# USB_Hub.net
KiCad netlist of a schematic drawn in Altium Designer
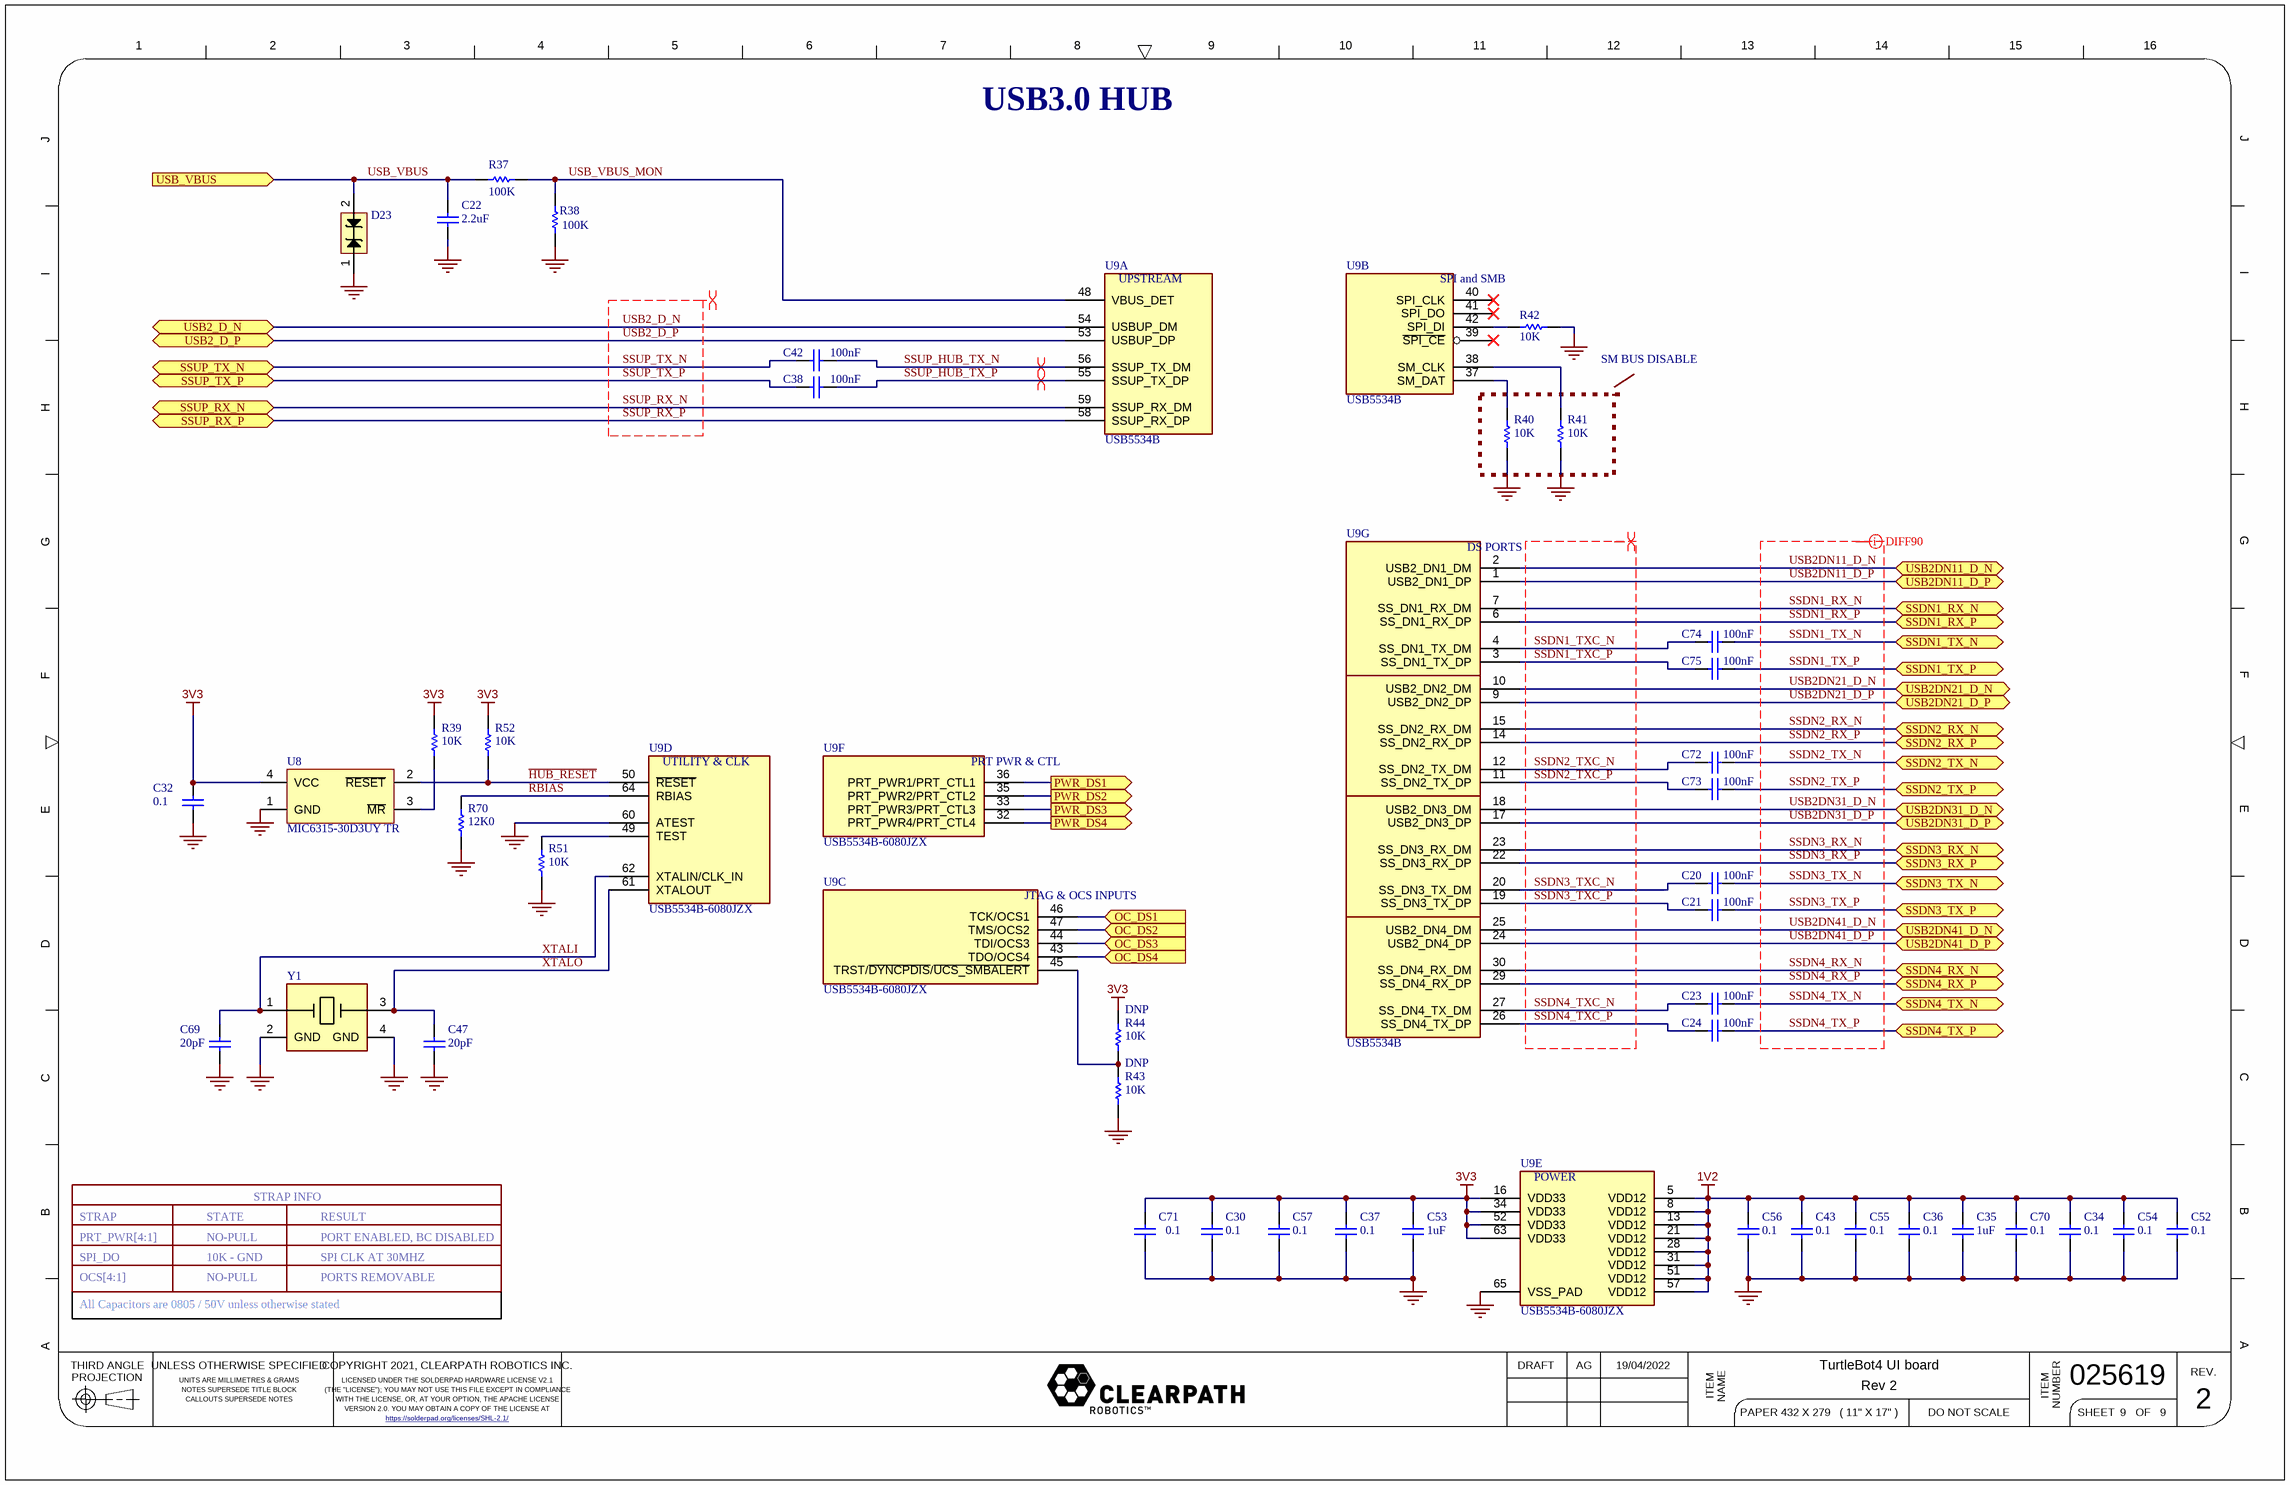
[diagram p0: USB Hub.SchDoc]

(export (version "E")
  (design (tool "Eeschema 10.0.6"))
  (components
    (comp (ref "C20")
      (value "100nF")
      (footprint "CAP 1608[0603]")
      (description "Capacitor")
      (fields (field (name "TOLERANCE") "10%") (field (name "VOLTAGE") "25V"))
      (libsource (lib "CPR_CommonDevices") (part "Capacitor _SMT"))
    )
    (comp (ref "C21")
      (value "100nF")
      (footprint "CAP 1608[0603]")
      (description "Capacitor")
      (fields (field (name "TOLERANCE") "10%") (field (name "VOLTAGE") "25V"))
      (libsource (lib "CPR_CommonDevices") (part "Capacitor _SMT"))
    )
    (comp (ref "C22")
      (value "2.2uF")
      (footprint "C0805")
      (description "Capacitor")
      (fields (field (name "TOLERANCE") "-20 +80") (field (name "VOLTAGE") "50V"))
      (libsource (lib "CPR_CommonDevices") (part "Capacitor _SMT"))
    )
    (comp (ref "C23")
      (value "100nF")
      (footprint "CAP 1608[0603]")
      (description "Capacitor")
      (fields (field (name "TOLERANCE") "10%") (field (name "VOLTAGE") "25V"))
      (libsource (lib "CPR_CommonDevices") (part "Capacitor _SMT"))
    )
    (comp (ref "C24")
      (value "100nF")
      (footprint "CAP 1608[0603]")
      (description "Capacitor")
      (fields (field (name "TOLERANCE") "10%") (field (name "VOLTAGE") "25V"))
      (libsource (lib "CPR_CommonDevices") (part "Capacitor _SMT"))
    )
    (comp (ref "C30")
      (value "0.1")
      (footprint "C0805")
      (description "Capacitor")
      (fields (field (name "TOLERANCE") "10%") (field (name "VOLTAGE") "50V"))
      (libsource (lib "CPR_CommonDevices") (part "Capacitor _SMT"))
    )
    (comp (ref "C32")
      (value "0.1")
      (footprint "C0805")
      (description "Capacitor")
      (fields (field (name "TOLERANCE") "10%") (field (name "VOLTAGE") "50V"))
      (libsource (lib "CPR_CommonDevices") (part "Capacitor _SMT"))
    )
    (comp (ref "C34")
      (value "0.1")
      (footprint "C0805")
      (description "Capacitor")
      (fields (field (name "TOLERANCE") "10%") (field (name "VOLTAGE") "50V"))
      (libsource (lib "CPR_CommonDevices") (part "Capacitor _SMT"))
    )
    (comp (ref "C35")
      (value "1uF")
      (footprint "C0805")
      (description "Capacitor")
      (fields (field (name "TOLERANCE") "-20 +80") (field (name "VOLTAGE") "50V"))
      (libsource (lib "CPR_CommonDevices") (part "Capacitor _SMT"))
    )
    (comp (ref "C36")
      (value "0.1")
      (footprint "C0805")
      (description "Capacitor")
      (fields (field (name "TOLERANCE") "10%") (field (name "VOLTAGE") "50V"))
      (libsource (lib "CPR_CommonDevices") (part "Capacitor _SMT"))
    )
    (comp (ref "C37")
      (value "0.1")
      (footprint "C0805")
      (description "Capacitor")
      (fields (field (name "TOLERANCE") "10%") (field (name "VOLTAGE") "50V"))
      (libsource (lib "CPR_CommonDevices") (part "Capacitor _SMT"))
    )
    (comp (ref "C38")
      (value "100nF")
      (footprint "CAP 1608[0603]")
      (description "Capacitor")
      (fields (field (name "TOLERANCE") "10%") (field (name "VOLTAGE") "25V"))
      (libsource (lib "CPR_CommonDevices") (part "Capacitor _SMT"))
    )
    (comp (ref "C42")
      (value "100nF")
      (footprint "CAP 1608[0603]")
      (description "Capacitor")
      (fields (field (name "TOLERANCE") "10%") (field (name "VOLTAGE") "25V"))
      (libsource (lib "CPR_CommonDevices") (part "Capacitor _SMT"))
    )
    (comp (ref "C43")
      (value "0.1")
      (footprint "C0805")
      (description "Capacitor")
      (fields (field (name "TOLERANCE") "10%") (field (name "VOLTAGE") "50V"))
      (libsource (lib "CPR_CommonDevices") (part "Capacitor _SMT"))
    )
    (comp (ref "C47")
      (value "20pF")
      (footprint "C0805")
      (description "Capacitor")
      (fields (field (name "TOLERANCE") "10%") (field (name "VOLTAGE") "50V"))
      (libsource (lib "CPR_CommonDevices") (part "Capacitor _SMT"))
    )
    (comp (ref "C52")
      (value "0.1")
      (footprint "C0805")
      (description "Capacitor")
      (fields (field (name "TOLERANCE") "10%") (field (name "VOLTAGE") "50V"))
      (libsource (lib "CPR_CommonDevices") (part "Capacitor _SMT"))
    )
    (comp (ref "C53")
      (value "1uF")
      (footprint "C0805")
      (description "Capacitor")
      (fields (field (name "TOLERANCE") "-20 +80") (field (name "VOLTAGE") "50V"))
      (libsource (lib "CPR_CommonDevices") (part "Capacitor _SMT"))
    )
    (comp (ref "C54")
      (value "0.1")
      (footprint "C0805")
      (description "Capacitor")
      (fields (field (name "TOLERANCE") "10%") (field (name "VOLTAGE") "50V"))
      (libsource (lib "CPR_CommonDevices") (part "Capacitor _SMT"))
    )
    (comp (ref "C55")
      (value "0.1")
      (footprint "C0805")
      (description "Capacitor")
      (fields (field (name "TOLERANCE") "10%") (field (name "VOLTAGE") "50V"))
      (libsource (lib "CPR_CommonDevices") (part "Capacitor _SMT"))
    )
    (comp (ref "C56")
      (value "0.1")
      (footprint "C0805")
      (description "Capacitor")
      (fields (field (name "TOLERANCE") "10%") (field (name "VOLTAGE") "50V"))
      (libsource (lib "CPR_CommonDevices") (part "Capacitor _SMT"))
    )
    (comp (ref "C57")
      (value "0.1")
      (footprint "C0805")
      (description "Capacitor")
      (fields (field (name "TOLERANCE") "10%") (field (name "VOLTAGE") "50V"))
      (libsource (lib "CPR_CommonDevices") (part "Capacitor _SMT"))
    )
    (comp (ref "C69")
      (value "20pF")
      (footprint "C0805")
      (description "Capacitor")
      (fields (field (name "TOLERANCE") "10%") (field (name "VOLTAGE") "50V"))
      (libsource (lib "CPR_CommonDevices") (part "Capacitor _SMT"))
    )
    (comp (ref "C70")
      (value "0.1")
      (footprint "C0805")
      (description "Capacitor")
      (fields (field (name "TOLERANCE") "10%") (field (name "VOLTAGE") "50V"))
      (libsource (lib "CPR_CommonDevices") (part "Capacitor _SMT"))
    )
    (comp (ref "C71")
      (value "0.1")
      (footprint "C0805")
      (description "Capacitor")
      (fields (field (name "TOLERANCE") "10%") (field (name "VOLTAGE") "50V"))
      (libsource (lib "CPR_CommonDevices") (part "Capacitor _SMT"))
    )
    (comp (ref "C72")
      (value "100nF")
      (footprint "CAP 1608[0603]")
      (description "Capacitor")
      (fields (field (name "TOLERANCE") "10%") (field (name "VOLTAGE") "25V"))
      (libsource (lib "CPR_CommonDevices") (part "Capacitor _SMT"))
    )
    (comp (ref "C73")
      (value "100nF")
      (footprint "CAP 1608[0603]")
      (description "Capacitor")
      (fields (field (name "TOLERANCE") "10%") (field (name "VOLTAGE") "25V"))
      (libsource (lib "CPR_CommonDevices") (part "Capacitor _SMT"))
    )
    (comp (ref "C74")
      (value "100nF")
      (footprint "CAP 1608[0603]")
      (description "Capacitor")
      (fields (field (name "TOLERANCE") "10%") (field (name "VOLTAGE") "25V"))
      (libsource (lib "CPR_CommonDevices") (part "Capacitor _SMT"))
    )
    (comp (ref "C75")
      (value "100nF")
      (footprint "CAP 1608[0603]")
      (description "Capacitor")
      (fields (field (name "TOLERANCE") "10%") (field (name "VOLTAGE") "25V"))
      (libsource (lib "CPR_CommonDevices") (part "Capacitor _SMT"))
    )
    (comp (ref "D23")
      (value "TVS DIODE BIDIR 15V SMC")
      (footprint "General PCB Library:DO-214AA")
      (description "TVS 600W 15V BI-DIR DO-214AA")
      (fields (field (name "MFG") "Littelfuse Inc."))
      (libsource (lib "SMBJ15CA") (part "TVS DIODE BIDIR 15V SMC"))
    )
    (comp (ref "R37")
      (value "100K")
      (footprint "R0805")
      (description "Resistor")
      (fields (field (name "TOLERANCE") "1%") (field (name "MFG") "Yageo"))
      (libsource (lib "CPR_CommonDevices") (part "Resistor_SMT"))
    )
    (comp (ref "R38")
      (value "100K")
      (footprint "R0805")
      (description "Resistor")
      (fields (field (name "TOLERANCE") "1%") (field (name "MFG") "Yageo"))
      (libsource (lib "CPR_CommonDevices") (part "Resistor_SMT"))
    )
    (comp (ref "R39")
      (value "10K")
      (footprint "R0805")
      (description "Resistor")
      (fields (field (name "TOLERANCE") "1%") (field (name "MFG") "Yageo"))
      (libsource (lib "CPR_CommonDevices") (part "Resistor_SMT"))
    )
    (comp (ref "R40")
      (value "10K")
      (footprint "R0805")
      (description "Resistor")
      (fields (field (name "TOLERANCE") "1%") (field (name "MFG") "Yageo"))
      (libsource (lib "CPR_CommonDevices") (part "Resistor_SMT"))
    )
    (comp (ref "R41")
      (value "10K")
      (footprint "R0805")
      (description "Resistor")
      (fields (field (name "TOLERANCE") "1%") (field (name "MFG") "Yageo"))
      (libsource (lib "CPR_CommonDevices") (part "Resistor_SMT"))
    )
    (comp (ref "R42")
      (value "10K")
      (footprint "R0805")
      (description "Resistor")
      (fields (field (name "TOLERANCE") "1%") (field (name "MFG") "Yageo"))
      (libsource (lib "CPR_CommonDevices") (part "Resistor_SMT"))
    )
    (comp (ref "R43")
      (value "10K")
      (footprint "R0805")
      (description "Resistor")
      (fields (field (name "TOLERANCE") "1%") (field (name "DNP") "DNP") (field (name "MFG") "Yageo"))
      (libsource (lib "CPR_CommonDevices") (part "Resistor_SMT"))
    )
    (comp (ref "R44")
      (value "10K")
      (footprint "R0805")
      (description "Resistor")
      (fields (field (name "TOLERANCE") "1%") (field (name "DNP") "DNP") (field (name "MFG") "Yageo"))
      (libsource (lib "CPR_CommonDevices") (part "Resistor_SMT"))
    )
    (comp (ref "R51")
      (value "10K")
      (footprint "R0805")
      (description "Resistor")
      (fields (field (name "TOLERANCE") "1%") (field (name "MFG") "Yageo"))
      (libsource (lib "CPR_CommonDevices") (part "Resistor_SMT"))
    )
    (comp (ref "R52")
      (value "10K")
      (footprint "R0805")
      (description "Resistor")
      (fields (field (name "TOLERANCE") "1%") (field (name "MFG") "Yageo"))
      (libsource (lib "CPR_CommonDevices") (part "Resistor_SMT"))
    )
    (comp (ref "R70")
      (value "12K0")
      (footprint "R0805")
      (description "Resistor")
      (fields (field (name "TOLERANCE") "1%") (field (name "MFG") "Yageo"))
      (libsource (lib "CPR_CommonDevices") (part "Resistor_SMT"))
    )
    (comp (ref "U8")
      (value "MIC6315")
      (footprint "SOT143 CPR")
      (description "IC RESET GEN 3.00V VTH SOT143-4")
      (fields (field (name "MFG") "Micrel") (field (name "MFG PN") "MIC6315-30D3UY TR"))
      (libsource (lib "Micrel") (part "MIC6315"))
    )
    (comp (ref "U9")
      (value "USB5534B")
      (footprint "QFN64_9x9_EP")
      (description "USB5534B 4-port USB3 hub")
      (fields (field (name "MFG") "Microchip") (field (name "MFG PN") "USB5534B-6080JZX"))
      (libsource (lib "USB5534B USB Hub") (part "USB5534B"))
    )
    (comp (ref "Y1")
      (value "ECS-250 crystal")
      (footprint "ECX-53B")
      (fields (field (name "MFG") "ECS"))
      (libsource (lib "ECX-53B XTAL") (part "ECS-250 crystal"))
    )
  )
  (nets
    (net (code "1") (name "/OC_DS1") (class "Default")
      (node (ref "U9") (pin "46") (pinfunction "TCK/OCS1_46") (pintype "passive"))
    )
    (net (code "2") (name "/OC_DS2") (class "Default")
      (node (ref "U9") (pin "47") (pinfunction "TMS/OCS2_47") (pintype "passive"))
    )
    (net (code "3") (name "/OC_DS3") (class "Default")
      (node (ref "U9") (pin "44") (pinfunction "TDI/OCS3_44") (pintype "passive"))
    )
    (net (code "4") (name "/OC_DS4") (class "Default")
      (node (ref "U9") (pin "43") (pinfunction "TDO/OCS4_43") (pintype "passive"))
    )
    (net (code "5") (name "/PWR_DS1") (class "Default")
      (node (ref "U9") (pin "36") (pinfunction "PRT_PWR1/PRT_CTL1_36") (pintype "passive"))
    )
    (net (code "6") (name "/PWR_DS2") (class "Default")
      (node (ref "U9") (pin "35") (pinfunction "PRT_PWR2/PRT_CTL2_35") (pintype "passive"))
    )
    (net (code "7") (name "/PWR_DS3") (class "Default")
      (node (ref "U9") (pin "33") (pinfunction "PRT_PWR3/PRT_CTL3_33") (pintype "passive"))
    )
    (net (code "8") (name "/PWR_DS4") (class "Default")
      (node (ref "U9") (pin "32") (pinfunction "PRT_PWR4/PRT_CTL4_32") (pintype "passive"))
    )
    (net (code "9") (name "/RBIAS") (class "Default")
      (node (ref "R70") (pin "1") (pinfunction "1_1") (pintype "passive"))
      (node (ref "U9") (pin "64") (pinfunction "RBIAS_64") (pintype "passive"))
    )
    (net (code "10") (name "/SSDN1_RX_N") (class "Default")
      (node (ref "U9") (pin "7") (pinfunction "SS_DN1_RX_DM_7") (pintype "passive"))
    )
    (net (code "11") (name "/SSDN1_RX_P") (class "Default")
      (node (ref "U9") (pin "6") (pinfunction "SS_DN1_RX_DP_6") (pintype "passive"))
    )
    (net (code "12") (name "/SSDN1_TXC_N") (class "Default")
      (node (ref "C74") (pin "1") (pinfunction "1_1") (pintype "passive"))
      (node (ref "U9") (pin "4") (pinfunction "SS_DN1_TX_DM_4") (pintype "passive"))
    )
    (net (code "13") (name "/SSDN1_TXC_P") (class "Default")
      (node (ref "C75") (pin "1") (pinfunction "1_1") (pintype "passive"))
      (node (ref "U9") (pin "3") (pinfunction "SS_DN1_TX_DP_3") (pintype "passive"))
    )
    (net (code "14") (name "/SSDN1_TX_N") (class "Default")
      (node (ref "C74") (pin "2") (pinfunction "2_2") (pintype "passive"))
    )
    (net (code "15") (name "/SSDN1_TX_P") (class "Default")
      (node (ref "C75") (pin "2") (pinfunction "2_2") (pintype "passive"))
    )
    (net (code "16") (name "/SSDN2_RX_N") (class "Default")
      (node (ref "U9") (pin "15") (pinfunction "SS_DN2_RX_DM_15") (pintype "passive"))
    )
    (net (code "17") (name "/SSDN2_RX_P") (class "Default")
      (node (ref "U9") (pin "14") (pinfunction "SS_DN2_RX_DP_14") (pintype "passive"))
    )
    (net (code "18") (name "/SSDN2_TXC_N") (class "Default")
      (node (ref "C72") (pin "1") (pinfunction "1_1") (pintype "passive"))
      (node (ref "U9") (pin "12") (pinfunction "SS_DN2_TX_DM_12") (pintype "passive"))
    )
    (net (code "19") (name "/SSDN2_TXC_P") (class "Default")
      (node (ref "C73") (pin "1") (pinfunction "1_1") (pintype "passive"))
      (node (ref "U9") (pin "11") (pinfunction "SS_DN2_TX_DP_11") (pintype "passive"))
    )
    (net (code "20") (name "/SSDN2_TX_N") (class "Default")
      (node (ref "C72") (pin "2") (pinfunction "2_2") (pintype "passive"))
    )
    (net (code "21") (name "/SSDN2_TX_P") (class "Default")
      (node (ref "C73") (pin "2") (pinfunction "2_2") (pintype "passive"))
    )
    (net (code "22") (name "/SSDN3_RX_N") (class "Default")
      (node (ref "U9") (pin "23") (pinfunction "SS_DN3_RX_DM_23") (pintype "passive"))
    )
    (net (code "23") (name "/SSDN3_RX_P") (class "Default")
      (node (ref "U9") (pin "22") (pinfunction "SS_DN3_RX_DP_22") (pintype "passive"))
    )
    (net (code "24") (name "/SSDN3_TXC_N") (class "Default")
      (node (ref "C20") (pin "1") (pinfunction "1_1") (pintype "passive"))
      (node (ref "U9") (pin "20") (pinfunction "SS_DN3_TX_DM_20") (pintype "passive"))
    )
    (net (code "25") (name "/SSDN3_TXC_P") (class "Default")
      (node (ref "C21") (pin "1") (pinfunction "1_1") (pintype "passive"))
      (node (ref "U9") (pin "19") (pinfunction "SS_DN3_TX_DP_19") (pintype "passive"))
    )
    (net (code "26") (name "/SSDN3_TX_N") (class "Default")
      (node (ref "C20") (pin "2") (pinfunction "2_2") (pintype "passive"))
    )
    (net (code "27") (name "/SSDN3_TX_P") (class "Default")
      (node (ref "C21") (pin "2") (pinfunction "2_2") (pintype "passive"))
    )
    (net (code "28") (name "/SSDN4_RX_N") (class "Default")
      (node (ref "U9") (pin "30") (pinfunction "SS_DN4_RX_DM_30") (pintype "passive"))
    )
    (net (code "29") (name "/SSDN4_RX_P") (class "Default")
      (node (ref "U9") (pin "29") (pinfunction "SS_DN4_RX_DP_29") (pintype "passive"))
    )
    (net (code "30") (name "/SSDN4_TXC_N") (class "Default")
      (node (ref "C23") (pin "1") (pinfunction "1_1") (pintype "passive"))
      (node (ref "U9") (pin "27") (pinfunction "SS_DN4_TX_DM_27") (pintype "passive"))
    )
    (net (code "31") (name "/SSDN4_TXC_P") (class "Default")
      (node (ref "C24") (pin "1") (pinfunction "1_1") (pintype "passive"))
      (node (ref "U9") (pin "26") (pinfunction "SS_DN4_TX_DP_26") (pintype "passive"))
    )
    (net (code "32") (name "/SSDN4_TX_N") (class "Default")
      (node (ref "C23") (pin "2") (pinfunction "2_2") (pintype "passive"))
    )
    (net (code "33") (name "/SSDN4_TX_P") (class "Default")
      (node (ref "C24") (pin "2") (pinfunction "2_2") (pintype "passive"))
    )
    (net (code "34") (name "/SSUP_HUB_TX_N") (class "Default")
      (node (ref "C42") (pin "2") (pinfunction "2_2") (pintype "passive"))
      (node (ref "U9") (pin "56") (pinfunction "SSUP_TX_DM_56") (pintype "passive"))
    )
    (net (code "35") (name "/SSUP_HUB_TX_P") (class "Default")
      (node (ref "C38") (pin "2") (pinfunction "2_2") (pintype "passive"))
      (node (ref "U9") (pin "55") (pinfunction "SSUP_TX_DP_55") (pintype "passive"))
    )
    (net (code "36") (name "/SSUP_RX_N") (class "Default")
      (node (ref "U9") (pin "59") (pinfunction "SSUP_RX_DM_59") (pintype "passive"))
    )
    (net (code "37") (name "/SSUP_RX_P") (class "Default")
      (node (ref "U9") (pin "58") (pinfunction "SSUP_RX_DP_58") (pintype "passive"))
    )
    (net (code "38") (name "/SSUP_TX_N") (class "Default")
      (node (ref "C42") (pin "1") (pinfunction "1_1") (pintype "passive"))
    )
    (net (code "39") (name "/SSUP_TX_P") (class "Default")
      (node (ref "C38") (pin "1") (pinfunction "1_1") (pintype "passive"))
    )
    (net (code "40") (name "/USB2DN11_D_N") (class "Default")
      (node (ref "U9") (pin "2") (pinfunction "USB2_DN1_DM_2") (pintype "passive"))
    )
    (net (code "41") (name "/USB2DN11_D_P") (class "Default")
      (node (ref "U9") (pin "1") (pinfunction "USB2_DN1_DP_1") (pintype "passive"))
    )
    (net (code "42") (name "/USB2DN21_D_N") (class "Default")
      (node (ref "U9") (pin "10") (pinfunction "USB2_DN2_DM_10") (pintype "passive"))
    )
    (net (code "43") (name "/USB2DN21_D_P") (class "Default")
      (node (ref "U9") (pin "9") (pinfunction "USB2_DN2_DP_9") (pintype "passive"))
    )
    (net (code "44") (name "/USB2DN31_D_N") (class "Default")
      (node (ref "U9") (pin "18") (pinfunction "USB2_DN3_DM_18") (pintype "passive"))
    )
    (net (code "45") (name "/USB2DN31_D_P") (class "Default")
      (node (ref "U9") (pin "17") (pinfunction "USB2_DN3_DP_17") (pintype "passive"))
    )
    (net (code "46") (name "/USB2DN41_D_N") (class "Default")
      (node (ref "U9") (pin "25") (pinfunction "USB2_DN4_DM_25") (pintype "passive"))
    )
    (net (code "47") (name "/USB2DN41_D_P") (class "Default")
      (node (ref "U9") (pin "24") (pinfunction "USB2_DN4_DP_24") (pintype "passive"))
    )
    (net (code "48") (name "/USB2_D_N") (class "Default")
      (node (ref "U9") (pin "54") (pinfunction "USBUP_DM_54") (pintype "passive"))
    )
    (net (code "49") (name "/USB2_D_P") (class "Default")
      (node (ref "U9") (pin "53") (pinfunction "USBUP_DP_53") (pintype "passive"))
    )
    (net (code "50") (name "/USB_VBUS") (class "Default")
      (node (ref "C22") (pin "2") (pinfunction "2_2") (pintype "passive"))
      (node (ref "D23") (pin "2") (pintype "passive"))
      (node (ref "R37") (pin "1") (pinfunction "1_1") (pintype "passive"))
    )
    (net (code "51") (name "/USB_VBUS_MON") (class "Default")
      (node (ref "R37") (pin "2") (pinfunction "2_2") (pintype "passive"))
      (node (ref "R38") (pin "2") (pinfunction "2_2") (pintype "passive"))
      (node (ref "U9") (pin "48") (pinfunction "VBUS_DET_48") (pintype "passive"))
    )
    (net (code "52") (name "/XTALI") (class "Default")
      (node (ref "C69") (pin "1") (pinfunction "1_1") (pintype "passive"))
      (node (ref "U9") (pin "62") (pinfunction "XTALIN/CLK_IN_62") (pintype "passive"))
      (node (ref "Y1") (pin "1") (pinfunction "0_1") (pintype "passive"))
    )
    (net (code "53") (name "/XTALO") (class "Default")
      (node (ref "C47") (pin "1") (pinfunction "1_1") (pintype "passive"))
      (node (ref "U9") (pin "61") (pinfunction "XTALOUT_61") (pintype "passive"))
      (node (ref "Y1") (pin "3") (pinfunction "1_3") (pintype "passive"))
    )
    (net (code "54") (name "/~{HUB_RESET}") (class "Default")
      (node (ref "R52") (pin "2") (pinfunction "2_2") (pintype "passive"))
      (node (ref "U8") (pin "2") (pinfunction "~{RESET}_2") (pintype "passive"))
      (node (ref "U9") (pin "50") (pinfunction "~{RESET}_50") (pintype "passive"))
    )
    (net (code "55") (name "1V2") (class "Default")
      (node (ref "C34") (pin "2") (pinfunction "2_2") (pintype "passive"))
      (node (ref "C35") (pin "2") (pinfunction "2_2") (pintype "passive"))
      (node (ref "C36") (pin "2") (pinfunction "2_2") (pintype "passive"))
      (node (ref "C43") (pin "2") (pinfunction "2_2") (pintype "passive"))
      (node (ref "C52") (pin "2") (pinfunction "2_2") (pintype "passive"))
      (node (ref "C54") (pin "2") (pinfunction "2_2") (pintype "passive"))
      (node (ref "C55") (pin "2") (pinfunction "2_2") (pintype "passive"))
      (node (ref "C56") (pin "2") (pinfunction "2_2") (pintype "passive"))
      (node (ref "C70") (pin "2") (pinfunction "2_2") (pintype "passive"))
      (node (ref "U9") (pin "13") (pinfunction "VDD12_13") (pintype "passive"))
      (node (ref "U9") (pin "21") (pinfunction "VDD12_21") (pintype "passive"))
      (node (ref "U9") (pin "28") (pinfunction "VDD12_28") (pintype "passive"))
      (node (ref "U9") (pin "31") (pinfunction "VDD12_31") (pintype "passive"))
      (node (ref "U9") (pin "5") (pinfunction "VDD12_5") (pintype "passive"))
      (node (ref "U9") (pin "51") (pinfunction "VDD12_51") (pintype "passive"))
      (node (ref "U9") (pin "57") (pinfunction "VDD12_57") (pintype "passive"))
      (node (ref "U9") (pin "8") (pinfunction "VDD12_8") (pintype "passive"))
    )
    (net (code "56") (name "3V3") (class "Default")
      (node (ref "C30") (pin "2") (pinfunction "2_2") (pintype "passive"))
      (node (ref "C32") (pin "2") (pinfunction "2_2") (pintype "passive"))
      (node (ref "C37") (pin "2") (pinfunction "2_2") (pintype "passive"))
      (node (ref "C53") (pin "2") (pinfunction "2_2") (pintype "passive"))
      (node (ref "C57") (pin "2") (pinfunction "2_2") (pintype "passive"))
      (node (ref "C71") (pin "2") (pinfunction "2_2") (pintype "passive"))
      (node (ref "R39") (pin "1") (pinfunction "1_1") (pintype "passive"))
      (node (ref "R44") (pin "1") (pinfunction "1_1") (pintype "passive"))
      (node (ref "R52") (pin "1") (pinfunction "1_1") (pintype "passive"))
      (node (ref "U8") (pin "4") (pinfunction "VCC_4") (pintype "passive"))
      (node (ref "U9") (pin "16") (pinfunction "VDD33_16") (pintype "passive"))
      (node (ref "U9") (pin "34") (pinfunction "VDD33_34") (pintype "passive"))
      (node (ref "U9") (pin "52") (pinfunction "VDD33_52") (pintype "passive"))
      (node (ref "U9") (pin "63") (pinfunction "VDD33_63") (pintype "passive"))
    )
    (net (code "57") (name "GND") (class "Default")
      (node (ref "C22") (pin "1") (pinfunction "1_1") (pintype "passive"))
      (node (ref "C30") (pin "1") (pinfunction "1_1") (pintype "passive"))
      (node (ref "C32") (pin "1") (pinfunction "1_1") (pintype "passive"))
      (node (ref "C34") (pin "1") (pinfunction "1_1") (pintype "passive"))
      (node (ref "C35") (pin "1") (pinfunction "1_1") (pintype "passive"))
      (node (ref "C36") (pin "1") (pinfunction "1_1") (pintype "passive"))
      (node (ref "C37") (pin "1") (pinfunction "1_1") (pintype "passive"))
      (node (ref "C43") (pin "1") (pinfunction "1_1") (pintype "passive"))
      (node (ref "C47") (pin "2") (pinfunction "2_2") (pintype "passive"))
      (node (ref "C52") (pin "1") (pinfunction "1_1") (pintype "passive"))
      (node (ref "C53") (pin "1") (pinfunction "1_1") (pintype "passive"))
      (node (ref "C54") (pin "1") (pinfunction "1_1") (pintype "passive"))
      (node (ref "C55") (pin "1") (pinfunction "1_1") (pintype "passive"))
      (node (ref "C56") (pin "1") (pinfunction "1_1") (pintype "passive"))
      (node (ref "C57") (pin "1") (pinfunction "1_1") (pintype "passive"))
      (node (ref "C69") (pin "2") (pinfunction "2_2") (pintype "passive"))
      (node (ref "C70") (pin "1") (pinfunction "1_1") (pintype "passive"))
      (node (ref "C71") (pin "1") (pinfunction "1_1") (pintype "passive"))
      (node (ref "D23") (pin "1") (pintype "passive"))
      (node (ref "R38") (pin "1") (pinfunction "1_1") (pintype "passive"))
      (node (ref "R40") (pin "2") (pinfunction "2_2") (pintype "passive"))
      (node (ref "R41") (pin "2") (pinfunction "2_2") (pintype "passive"))
      (node (ref "R42") (pin "2") (pinfunction "2_2") (pintype "passive"))
      (node (ref "R43") (pin "2") (pinfunction "2_2") (pintype "passive"))
      (node (ref "R51") (pin "2") (pinfunction "2_2") (pintype "passive"))
      (node (ref "R70") (pin "2") (pinfunction "2_2") (pintype "passive"))
      (node (ref "U8") (pin "1") (pinfunction "GND_1") (pintype "passive"))
      (node (ref "U9") (pin "60") (pinfunction "ATEST_60") (pintype "passive"))
      (node (ref "U9") (pin "65") (pinfunction "VSS_PAD_65") (pintype "passive"))
      (node (ref "Y1") (pin "2") (pinfunction "GND_2") (pintype "passive"))
      (node (ref "Y1") (pin "4") (pinfunction "GND_4") (pintype "passive"))
    )
    (net (code "58") (name "Net-(U8-~{MR})") (class "Default")
      (node (ref "R39") (pin "2") (pinfunction "2_2") (pintype "passive"))
      (node (ref "U8") (pin "3") (pinfunction "~{MR}_3") (pintype "passive"))
    )
    (net (code "59") (name "Net-(U9B-SM_CLK)") (class "Default")
      (node (ref "R41") (pin "1") (pinfunction "1_1") (pintype "passive"))
      (node (ref "U9") (pin "38") (pinfunction "SM_CLK_38") (pintype "passive"))
    )
    (net (code "60") (name "Net-(U9B-SM_DAT)") (class "Default")
      (node (ref "R40") (pin "1") (pinfunction "1_1") (pintype "passive"))
      (node (ref "U9") (pin "37") (pinfunction "SM_DAT_37") (pintype "passive"))
    )
    (net (code "61") (name "Net-(U9B-SPI_DI)") (class "Default")
      (node (ref "R42") (pin "1") (pinfunction "1_1") (pintype "passive"))
      (node (ref "U9") (pin "42") (pinfunction "SPI_DI_42") (pintype "passive"))
    )
    (net (code "62") (name "Net-(U9C-TRST{slash}~{DYNCPDIS}{slash}~{UCS_SMBALERT})") (class "Default")
      (node (ref "R43") (pin "1") (pinfunction "1_1") (pintype "passive"))
      (node (ref "R44") (pin "2") (pinfunction "2_2") (pintype "passive"))
      (node (ref "U9") (pin "45") (pinfunction "TRST/~{DYNCPDIS}/~{UCS_SMBALERT}_45") (pintype "passive"))
    )
    (net (code "63") (name "Net-(U9D-TEST)") (class "Default")
      (node (ref "R51") (pin "1") (pinfunction "1_1") (pintype "passive"))
      (node (ref "U9") (pin "49") (pinfunction "TEST_49") (pintype "passive"))
    )
    (net (code "64") (name "unconnected-(U9B-SPI_CLK-Pad40)") (class "Default")
      (node (ref "U9") (pin "40") (pinfunction "SPI_CLK_40") (pintype "passive+no_connect"))
    )
    (net (code "65") (name "unconnected-(U9B-SPI_DO-Pad41)") (class "Default")
      (node (ref "U9") (pin "41") (pinfunction "SPI_DO_41") (pintype "passive+no_connect"))
    )
    (net (code "66") (name "unconnected-(U9B-~{SPI_CE}-Pad39)") (class "Default")
      (node (ref "U9") (pin "39") (pinfunction "~{SPI_CE}_39") (pintype "passive+no_connect"))
    )
  )
)
